# AlcoTop.net
KiCad netlist of a schematic drawn in EAGLE
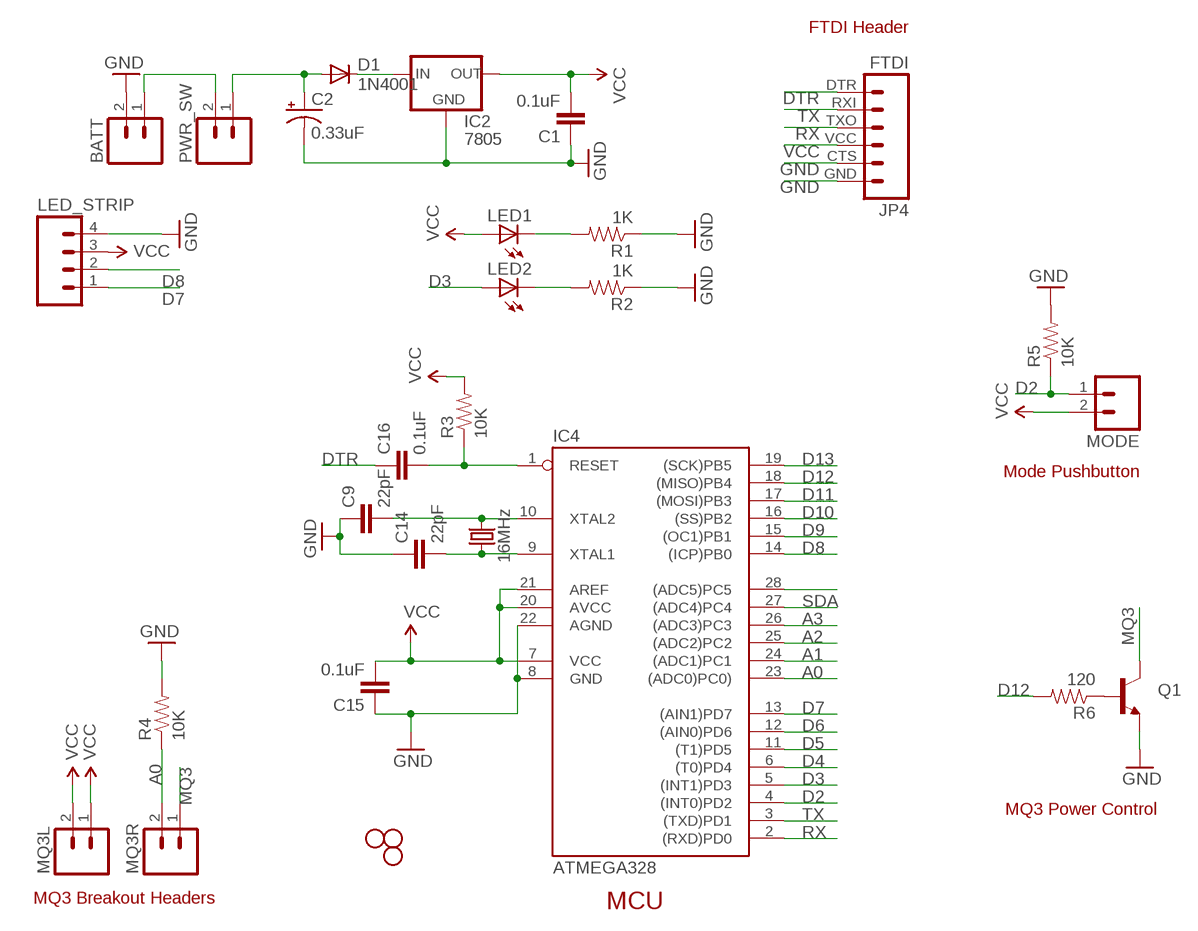
[diagram p0: schematic, sheet 1]

(export (version "E")
  (design (tool "Eeschema 10.0.6"))
  (components
    (comp (ref "BATT")
      (value "M02LOCK_LONGPADS")
      (footprint "eagle-import:1X02_LOCK_LONGPADS")
      (libsource (lib "eagle-import") (part "M02LOCK_LONGPADS"))
    )
    (comp (ref "C1")
      (value "0.1uF")
      (footprint "eagle-import:CAP-PTH-SMALL2")
      (libsource (lib "eagle-import") (part "CAPPTH2"))
    )
    (comp (ref "C2")
      (value "0.33uF")
      (footprint "eagle-import:CPOL-RADIAL-10UF-25V")
      (libsource (lib "eagle-import") (part "CAP_POLPTH2"))
    )
    (comp (ref "C9")
      (value "22pF")
      (footprint "eagle-import:CAP-PTH-SMALL2")
      (libsource (lib "eagle-import") (part "CAPPTH2"))
    )
    (comp (ref "C14")
      (value "22pF")
      (footprint "eagle-import:CAP-PTH-SMALL2")
      (libsource (lib "eagle-import") (part "CAPPTH2"))
    )
    (comp (ref "C15")
      (value "0.1uF")
      (footprint "eagle-import:CAP-PTH-SMALL2")
      (libsource (lib "eagle-import") (part "CAPPTH2"))
    )
    (comp (ref "C16")
      (value "0.1uF")
      (footprint "eagle-import:CAP-PTH-SMALL2")
      (libsource (lib "eagle-import") (part "CAPPTH2"))
    )
    (comp (ref "D1")
      (value "1N4001")
      (footprint "eagle-import:DIODE-1N4001")
      (libsource (lib "eagle-import") (part "DIODEPTH"))
    )
    (comp (ref "IC2")
      (value "7805")
      (footprint "eagle-import:TO220-IGO")
      (libsource (lib "eagle-import") (part "V_REG_78XXSINK"))
    )
    (comp (ref "IC4")
      (value "ATMEGA328")
      (footprint "eagle-import:DIL28-3")
      (libsource (lib "eagle-import") (part "AT90S4433P"))
    )
    (comp (ref "JP1")
      (value "STAND-OFF#2")
      (footprint "eagle-import:STAND-OFF-#2")
      (libsource (lib "eagle-import") (part "STAND-OFF#2"))
    )
    (comp (ref "JP2")
      (value "STAND-OFF#2")
      (footprint "eagle-import:STAND-OFF-#2")
      (libsource (lib "eagle-import") (part "STAND-OFF#2"))
    )
    (comp (ref "JP4")
      (value "FTDI")
      (footprint "eagle-import:FTDI_BASIC")
      (libsource (lib "eagle-import") (part "FTDI_BASICPTH"))
    )
    (comp (ref "JP6")
      (value "STAND-OFF#2")
      (footprint "eagle-import:STAND-OFF-#2")
      (libsource (lib "eagle-import") (part "STAND-OFF#2"))
    )
    (comp (ref "LED1")
      (value "LED5MM")
      (footprint "eagle-import:LED5MM")
      (libsource (lib "eagle-import") (part "LED5MM"))
    )
    (comp (ref "LED2")
      (value "LED5MM")
      (footprint "eagle-import:LED5MM")
      (libsource (lib "eagle-import") (part "LED5MM"))
    )
    (comp (ref "LED_STRIP")
      (value "M04LOCK_LONGPADS")
      (footprint "eagle-import:1X04_LOCK_LONGPADS")
      (libsource (lib "eagle-import") (part "M04LOCK_LONGPADS"))
    )
    (comp (ref "MODE")
      (value "M02LOCK_LONGPADS")
      (footprint "eagle-import:1X02_LOCK_LONGPADS")
      (libsource (lib "eagle-import") (part "M02LOCK_LONGPADS"))
    )
    (comp (ref "MQ3L")
      (value "M02LOCK_LONGPADS")
      (footprint "eagle-import:1X02_LOCK_LONGPADS")
      (libsource (lib "eagle-import") (part "M02LOCK_LONGPADS"))
    )
    (comp (ref "MQ3R")
      (value "M02LOCK_LONGPADS")
      (footprint "eagle-import:1X02_LOCK_LONGPADS")
      (libsource (lib "eagle-import") (part "M02LOCK_LONGPADS"))
    )
    (comp (ref "PWR_SW")
      (value "M02LOCK_LONGPADS")
      (footprint "eagle-import:1X02_LOCK_LONGPADS")
      (libsource (lib "eagle-import") (part "M02LOCK_LONGPADS"))
    )
    (comp (ref "Q1")
      (value "TRANSISTOR_NPNTO-92-AMMO")
      (footprint "eagle-import:TO-92-AMMO")
      (libsource (lib "eagle-import") (part "TRANSISTOR_NPNTO-92-AMMO"))
    )
    (comp (ref "R1")
      (value "1K")
      (footprint "eagle-import:AXIAL-0.3")
      (libsource (lib "eagle-import") (part "RESISTORAXIAL-0.3"))
    )
    (comp (ref "R2")
      (value "1K")
      (footprint "eagle-import:AXIAL-0.3")
      (libsource (lib "eagle-import") (part "RESISTORAXIAL-0.3"))
    )
    (comp (ref "R3")
      (value "10K")
      (footprint "eagle-import:AXIAL-0.3")
      (libsource (lib "eagle-import") (part "RESISTORAXIAL-0.3"))
    )
    (comp (ref "R4")
      (value "10K")
      (footprint "eagle-import:AXIAL-0.3")
      (libsource (lib "eagle-import") (part "RESISTORAXIAL-0.3"))
    )
    (comp (ref "R5")
      (value "10K")
      (footprint "eagle-import:AXIAL-0.3")
      (libsource (lib "eagle-import") (part "RESISTORAXIAL-0.3"))
    )
    (comp (ref "R6")
      (value "120")
      (footprint "eagle-import:AXIAL-0.3")
      (libsource (lib "eagle-import") (part "RESISTORAXIAL-0.3"))
    )
    (comp (ref "Y1")
      (value "16MHz")
      (footprint "eagle-import:HC49US")
      (libsource (lib "eagle-import") (part "CRYSTALHC49US"))
    )
  )
  (nets
    (net (code "1") (name "/A0") (class "Default")
      (node (ref "IC4") (pin "23") (pinfunction "(ADC0)PC0)_23") (pintype "bidirectional"))
      (node (ref "MQ3R") (pin "2") (pinfunction "2_2") (pintype "passive"))
      (node (ref "R4") (pin "P$1") (pinfunction "1_P$1") (pintype "passive"))
    )
    (net (code "2") (name "/A1") (class "Default")
      (node (ref "IC4") (pin "24") (pinfunction "(ADC1)PC1_24") (pintype "bidirectional"))
    )
    (net (code "3") (name "/A2") (class "Default")
      (node (ref "IC4") (pin "25") (pinfunction "(ADC2)PC2_25") (pintype "bidirectional"))
    )
    (net (code "4") (name "/A3") (class "Default")
      (node (ref "IC4") (pin "26") (pinfunction "(ADC3)PC3_26") (pintype "bidirectional"))
    )
    (net (code "5") (name "/D2") (class "Default")
      (node (ref "IC4") (pin "4") (pinfunction "(INT0)PD2_4") (pintype "bidirectional"))
      (node (ref "MODE") (pin "1") (pinfunction "1_1") (pintype "passive"))
      (node (ref "R5") (pin "P$1") (pinfunction "1_P$1") (pintype "passive"))
    )
    (net (code "6") (name "/D3") (class "Default")
      (node (ref "IC4") (pin "5") (pinfunction "(INT1)PD3_5") (pintype "bidirectional"))
      (node (ref "LED2") (pin "A") (pinfunction "A_A") (pintype "passive"))
    )
    (net (code "7") (name "/D4") (class "Default")
      (node (ref "IC4") (pin "6") (pinfunction "(T0)PD4_6") (pintype "bidirectional"))
    )
    (net (code "8") (name "/D5") (class "Default")
      (node (ref "IC4") (pin "11") (pinfunction "(T1)PD5_11") (pintype "bidirectional"))
    )
    (net (code "9") (name "/D6") (class "Default")
      (node (ref "IC4") (pin "12") (pinfunction "(AIN0)PD6_12") (pintype "bidirectional"))
    )
    (net (code "10") (name "/D7") (class "Default")
      (node (ref "IC4") (pin "13") (pinfunction "(AIN1)PD7_13") (pintype "bidirectional"))
      (node (ref "LED_STRIP") (pin "1") (pinfunction "1_1") (pintype "passive"))
    )
    (net (code "11") (name "/D8") (class "Default")
      (node (ref "IC4") (pin "14") (pinfunction "(ICP)PB0_14") (pintype "bidirectional"))
      (node (ref "LED_STRIP") (pin "2") (pinfunction "2_2") (pintype "passive"))
    )
    (net (code "12") (name "/D9") (class "Default")
      (node (ref "IC4") (pin "15") (pinfunction "(OC1)PB1_15") (pintype "bidirectional"))
    )
    (net (code "13") (name "/D10") (class "Default")
      (node (ref "IC4") (pin "16") (pinfunction "(SS)PB2_16") (pintype "bidirectional"))
    )
    (net (code "14") (name "/D11") (class "Default")
      (node (ref "IC4") (pin "17") (pinfunction "(MOSI)PB3_17") (pintype "bidirectional"))
    )
    (net (code "15") (name "/D12") (class "Default")
      (node (ref "IC4") (pin "18") (pinfunction "(MISO)PB4_18") (pintype "bidirectional"))
      (node (ref "R6") (pin "P$2") (pinfunction "2_P$2") (pintype "passive"))
    )
    (net (code "16") (name "/D13") (class "Default")
      (node (ref "IC4") (pin "19") (pinfunction "(SCK)PB5_19") (pintype "bidirectional"))
    )
    (net (code "17") (name "/DTR") (class "Default")
      (node (ref "C16") (pin "1") (pinfunction "1_1") (pintype "passive"))
      (node (ref "JP4") (pin "DTR") (pinfunction "1_DTR") (pintype "passive"))
    )
    (net (code "18") (name "/MQ3") (class "Default")
      (node (ref "MQ3R") (pin "1") (pinfunction "1_1") (pintype "passive"))
      (node (ref "Q1") (pin "3") (pinfunction "C_3") (pintype "passive"))
    )
    (net (code "19") (name "/RX") (class "Default")
      (node (ref "IC4") (pin "2") (pinfunction "(RXD)PD0_2") (pintype "bidirectional"))
      (node (ref "JP4") (pin "TXO") (pinfunction "3_TXO") (pintype "passive"))
    )
    (net (code "20") (name "/SDA") (class "Default")
      (node (ref "IC4") (pin "27") (pinfunction "(ADC4)PC4_27") (pintype "bidirectional"))
    )
    (net (code "21") (name "/TX") (class "Default")
      (node (ref "IC4") (pin "3") (pinfunction "(TXD)PD1_3") (pintype "bidirectional"))
      (node (ref "JP4") (pin "RXI") (pinfunction "2_RXI") (pintype "passive"))
    )
    (net (code "22") (name "GND") (class "Default")
      (node (ref "BATT") (pin "2") (pinfunction "2_2") (pintype "passive"))
      (node (ref "C1") (pin "1") (pinfunction "1_1") (pintype "passive"))
      (node (ref "C14") (pin "1") (pinfunction "1_1") (pintype "passive"))
      (node (ref "C15") (pin "1") (pinfunction "1_1") (pintype "passive"))
      (node (ref "C2") (pin "2") (pinfunction "-_2") (pintype "passive"))
      (node (ref "C9") (pin "1") (pinfunction "1_1") (pintype "passive"))
      (node (ref "IC2") (pin "GND") (pinfunction "GND_GND") (pintype "input"))
      (node (ref "IC4") (pin "22") (pinfunction "AGND_22") (pintype "power_in"))
      (node (ref "IC4") (pin "8") (pinfunction "GND_8") (pintype "power_in"))
      (node (ref "JP4") (pin "CTS") (pinfunction "5_CTS") (pintype "passive"))
      (node (ref "JP4") (pin "GND") (pinfunction "6_GND") (pintype "passive"))
      (node (ref "LED_STRIP") (pin "4") (pinfunction "4_4") (pintype "passive"))
      (node (ref "Q1") (pin "1") (pinfunction "E_1") (pintype "passive"))
      (node (ref "R1") (pin "P$1") (pinfunction "1_P$1") (pintype "passive"))
      (node (ref "R2") (pin "P$1") (pinfunction "1_P$1") (pintype "passive"))
      (node (ref "R4") (pin "P$2") (pinfunction "2_P$2") (pintype "passive"))
      (node (ref "R5") (pin "P$2") (pinfunction "2_P$2") (pintype "passive"))
    )
    (net (code "23") (name "Net-(BATT-Pad1)") (class "Default")
      (node (ref "BATT") (pin "1") (pinfunction "1_1") (pintype "passive"))
      (node (ref "PWR_SW") (pin "2") (pinfunction "2_2") (pintype "passive"))
    )
    (net (code "24") (name "Net-(C2-+)") (class "Default")
      (node (ref "C2") (pin "1") (pinfunction "+_1") (pintype "passive"))
      (node (ref "D1") (pin "A") (pinfunction "A_A") (pintype "passive"))
      (node (ref "PWR_SW") (pin "1") (pinfunction "1_1") (pintype "passive"))
    )
    (net (code "25") (name "Net-(D1-PadC)") (class "Default")
      (node (ref "D1") (pin "C") (pinfunction "C_C") (pintype "passive"))
      (node (ref "IC2") (pin "IN") (pinfunction "IN_IN") (pintype "input"))
    )
    (net (code "26") (name "Net-(IC4-RESET)") (class "Default")
      (node (ref "C16") (pin "2") (pinfunction "2_2") (pintype "passive"))
      (node (ref "IC4") (pin "1") (pinfunction "RESET_1") (pintype "input"))
      (node (ref "R3") (pin "P$1") (pinfunction "1_P$1") (pintype "passive"))
    )
    (net (code "27") (name "Net-(IC4-XTAL1)") (class "Default")
      (node (ref "C14") (pin "2") (pinfunction "2_2") (pintype "passive"))
      (node (ref "IC4") (pin "9") (pinfunction "XTAL1_9") (pintype "bidirectional"))
      (node (ref "Y1") (pin "1") (pinfunction "1_1") (pintype "passive"))
    )
    (net (code "28") (name "Net-(IC4-XTAL2)") (class "Default")
      (node (ref "C9") (pin "2") (pinfunction "2_2") (pintype "passive"))
      (node (ref "IC4") (pin "10") (pinfunction "XTAL2_10") (pintype "bidirectional"))
      (node (ref "Y1") (pin "2") (pinfunction "2_2") (pintype "passive"))
    )
    (net (code "29") (name "Net-(LED1-C)") (class "Default")
      (node (ref "LED1") (pin "K") (pinfunction "C_K") (pintype "passive"))
      (node (ref "R1") (pin "P$2") (pinfunction "2_P$2") (pintype "passive"))
    )
    (net (code "30") (name "Net-(LED2-C)") (class "Default")
      (node (ref "LED2") (pin "K") (pinfunction "C_K") (pintype "passive"))
      (node (ref "R2") (pin "P$2") (pinfunction "2_P$2") (pintype "passive"))
    )
    (net (code "31") (name "Net-(Q1-B)") (class "Default")
      (node (ref "Q1") (pin "2") (pinfunction "B_2") (pintype "passive"))
      (node (ref "R6") (pin "P$1") (pinfunction "1_P$1") (pintype "passive"))
    )
    (net (code "32") (name "VCC") (class "Default")
      (node (ref "C1") (pin "2") (pinfunction "2_2") (pintype "passive"))
      (node (ref "C15") (pin "2") (pinfunction "2_2") (pintype "passive"))
      (node (ref "IC2") (pin "OUT") (pinfunction "OUT_OUT") (pintype "output"))
      (node (ref "IC4") (pin "20") (pinfunction "AVCC_20") (pintype "power_in"))
      (node (ref "IC4") (pin "21") (pinfunction "AREF_21") (pintype "passive"))
      (node (ref "IC4") (pin "7") (pinfunction "VCC_7") (pintype "power_in"))
      (node (ref "JP4") (pin "VCC") (pinfunction "4_VCC") (pintype "passive"))
      (node (ref "LED1") (pin "A") (pinfunction "A_A") (pintype "passive"))
      (node (ref "LED_STRIP") (pin "3") (pinfunction "3_3") (pintype "passive"))
      (node (ref "MODE") (pin "2") (pinfunction "2_2") (pintype "passive"))
      (node (ref "MQ3L") (pin "1") (pinfunction "1_1") (pintype "passive"))
      (node (ref "MQ3L") (pin "2") (pinfunction "2_2") (pintype "passive"))
      (node (ref "R3") (pin "P$2") (pinfunction "2_P$2") (pintype "passive"))
    )
    (net (code "33") (name "unconnected-(IC4-(ADC5)PC5-Pad28)") (class "Default")
      (node (ref "IC4") (pin "28") (pinfunction "(ADC5)PC5_28") (pintype "bidirectional"))
    )
  )
)
